# CAN.net
KiCad netlist of a schematic drawn in Altium Designer
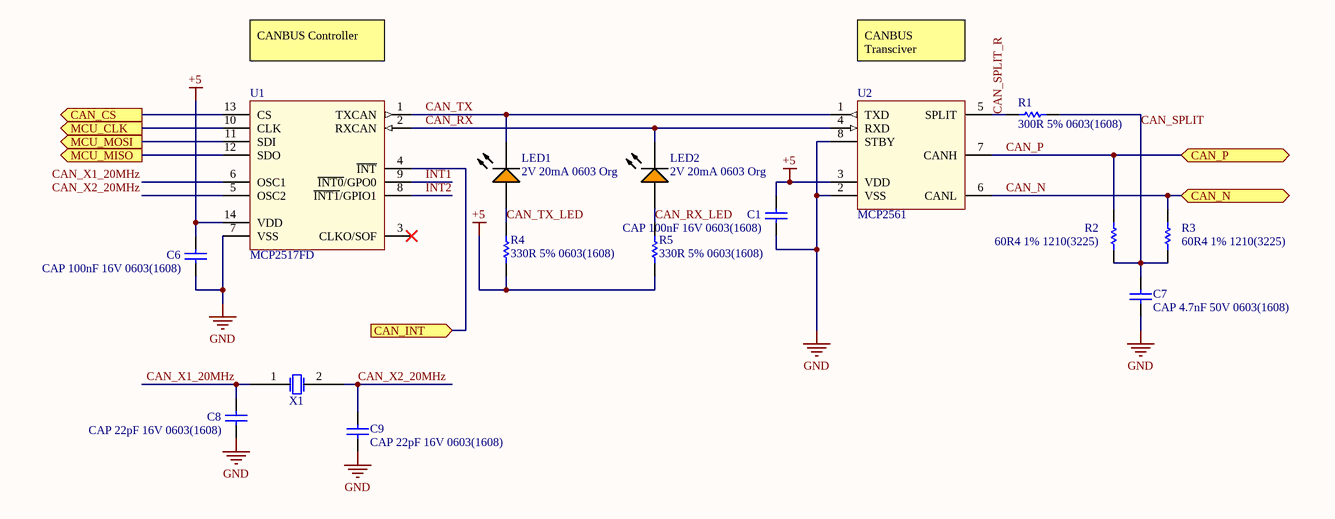
[diagram p0: CAN.SchDoc]

(export (version "E")
  (design (tool "Eeschema 10.0.6"))
  (components
    (comp (ref "C1")
      (value "CAP 100nF 16V 0603(1608)")
      (footprint "CAPC0603(1608)100_N")
      (description "CAP 100nF 16V ±10% 0603 (1608 Metric) Thickness 1mm SMD")
      (fields (field (name "TOLERANCE") "Â±10%"))
      (libsource (lib "Altium Content Vault") (part "CAP"))
    )
    (comp (ref "C6")
      (value "CAP 100nF 16V 0603(1608)")
      (footprint "CAPC0603(1608)100_N")
      (description "CAP 100nF 16V ±10% 0603 (1608 Metric) Thickness 1mm SMD")
      (fields (field (name "TOLERANCE") "Â±10%"))
      (libsource (lib "Altium Content Vault") (part "CAP"))
    )
    (comp (ref "C7")
      (value "CAP 4.7nF 50V 0603(1608)")
      (footprint "CAPC0603(1608)100_M")
      (description "CAP 4.7nF 50V ±5% 0603 (1608 Metric) Thickness 1mm SMD")
      (fields (field (name "TOLERANCE") "Â±5%"))
      (libsource (lib "Altium Content Vault") (part "CAP"))
    )
    (comp (ref "C8")
      (value "CAP 22pF 16V 0603(1608)")
      (footprint "CAPC0603(1608)100_N")
      (description "CAP 22pF 16V ±5% 0603 (1608 Metric) Thickness 1mm SMD")
      (fields (field (name "TOLERANCE") "Â±5%"))
      (libsource (lib "Altium Content Vault") (part "CAP"))
    )
    (comp (ref "C9")
      (value "CAP 22pF 16V 0603(1608)")
      (footprint "CAPC0603(1608)100_N")
      (description "CAP 22pF 16V ±5% 0603 (1608 Metric) Thickness 1mm SMD")
      (fields (field (name "TOLERANCE") "Â±5%"))
      (libsource (lib "Altium Content Vault") (part "CAP"))
    )
    (comp (ref "LED1")
      (value "2V 20mA 0603 Org")
      (footprint "KING-LED0603-25-ORANGE_V")
      (description "LED, SMT, 0603(1608), 0.25mm Tthickness, Super Bright Orange")
      (fields (field (name "PARTNUMBER") "APG1608SEKC/T"))
      (libsource (lib "Altium Content Vault") (part "KING-LED_ORANGE_A1K2-2"))
    )
    (comp (ref "LED2")
      (value "2V 20mA 0603 Org")
      (footprint "KING-LED0603-25-ORANGE_V")
      (description "LED, SMT, 0603(1608), 0.25mm Tthickness, Super Bright Orange")
      (fields (field (name "PARTNUMBER") "APG1608SEKC/T"))
      (libsource (lib "Altium Content Vault") (part "KING-LED_ORANGE_A1K2-2"))
    )
    (comp (ref "R1")
      (value "300R 5% 0603(1608)")
      (footprint "RESC0603(1608)_N")
      (description "300R 0.1W 5% 0603 (1608 Metric)  SMD")
      (fields (field (name "TOLERANCE") "5 %") (field (name "POWER") "0.1 W"))
      (libsource (lib "Altium Content Vault") (part "RES"))
    )
    (comp (ref "R2")
      (value "60R4 1% 1210(3225)")
      (footprint "RESC1210(3225)_L")
      (description "60R4 0.5W 1% 1210 (3225 Metric)  SMD")
      (fields (field (name "TOLERANCE") "1 %") (field (name "POWER") "0.5 W"))
      (libsource (lib "Altium Content Vault") (part "RES"))
    )
    (comp (ref "R3")
      (value "60R4 1% 1210(3225)")
      (footprint "RESC1210(3225)_L")
      (description "60R4 0.5W 1% 1210 (3225 Metric)  SMD")
      (fields (field (name "TOLERANCE") "1 %") (field (name "POWER") "0.5 W"))
      (libsource (lib "Altium Content Vault") (part "RES"))
    )
    (comp (ref "R4")
      (value "330R 5% 0603(1608)")
      (footprint "RESC0603(1608)_L")
      (description "330R 0.1W 5% 0603 (1608 Metric)  SMD")
      (fields (field (name "TOLERANCE") "5 %") (field (name "POWER") "0.1 W"))
      (libsource (lib "Altium Content Vault") (part "RES"))
    )
    (comp (ref "R5")
      (value "330R 5% 0603(1608)")
      (footprint "RESC0603(1608)_L")
      (description "330R 0.1W 5% 0603 (1608 Metric)  SMD")
      (fields (field (name "TOLERANCE") "5 %") (field (name "POWER") "0.1 W"))
      (libsource (lib "Altium Content Vault") (part "RES"))
    )
    (comp (ref "U1")
      (value "MCP2517FD")
      (footprint "MCP2517FD SOIC")
      (libsource (lib "QUTMS_CANLibrary") (part "MCP2517FD"))
    )
    (comp (ref "U2")
      (value "MCP2561")
      (footprint "MCP2561 SOIC")
      (libsource (lib "QUTMS_CANLibrary") (part "MCP2561"))
    )
    (comp (ref "X1")
      (value "Crystal 20MHz")
      (footprint "Crystal 20MHz")
      (libsource (lib "QUTMS_CrystalLibrary") (part "Crystal 20MHz"))
    )
  )
  (nets
    (net (code "1") (name "+5") (class "Default")
      (node (ref "C1") (pin "2") (pinfunction "2_2") (pintype "passive"))
      (node (ref "C6") (pin "2") (pinfunction "2_2") (pintype "passive"))
      (node (ref "R4") (pin "2") (pinfunction "2_2") (pintype "passive"))
      (node (ref "R5") (pin "2") (pinfunction "2_2") (pintype "passive"))
      (node (ref "U1") (pin "14") (pinfunction "VDD_14") (pintype "passive"))
      (node (ref "U2") (pin "3") (pinfunction "VDD_3") (pintype "passive"))
    )
    (net (code "2") (name "/CAN_CS") (class "Default")
      (node (ref "U1") (pin "13") (pinfunction "CS_13") (pintype "passive"))
    )
    (net (code "3") (name "/CAN_INT") (class "Default")
      (node (ref "U1") (pin "4") (pinfunction "~{INT}_4") (pintype "passive"))
    )
    (net (code "4") (name "/CAN_N") (class "Default")
      (node (ref "R3") (pin "2") (pinfunction "2_2") (pintype "passive"))
      (node (ref "U2") (pin "6") (pinfunction "CANL_6") (pintype "passive"))
    )
    (net (code "5") (name "/CAN_P") (class "Default")
      (node (ref "R2") (pin "2") (pinfunction "2_2") (pintype "passive"))
      (node (ref "U2") (pin "7") (pinfunction "CANH_7") (pintype "passive"))
    )
    (net (code "6") (name "/CAN_RX") (class "Default")
      (node (ref "LED2") (pin "2") (pinfunction "K_2") (pintype "passive"))
      (node (ref "U1") (pin "2") (pinfunction "RXCAN_2") (pintype "input"))
      (node (ref "U2") (pin "4") (pinfunction "RXD_4") (pintype "input"))
    )
    (net (code "7") (name "/CAN_RX_LED") (class "Default")
      (node (ref "LED2") (pin "1") (pinfunction "A_1") (pintype "passive"))
      (node (ref "R5") (pin "1") (pinfunction "1_1") (pintype "passive"))
    )
    (net (code "8") (name "/CAN_SPLIT") (class "Default")
      (node (ref "C7") (pin "2") (pinfunction "2_2") (pintype "passive"))
      (node (ref "R1") (pin "2") (pinfunction "2_2") (pintype "passive"))
      (node (ref "R2") (pin "1") (pinfunction "1_1") (pintype "passive"))
      (node (ref "R3") (pin "1") (pinfunction "1_1") (pintype "passive"))
    )
    (net (code "9") (name "/CAN_SPLIT_R") (class "Default")
      (node (ref "R1") (pin "1") (pinfunction "1_1") (pintype "passive"))
      (node (ref "U2") (pin "5") (pinfunction "SPLIT_5") (pintype "passive"))
    )
    (net (code "10") (name "/CAN_TX") (class "Default")
      (node (ref "LED1") (pin "2") (pinfunction "K_2") (pintype "passive"))
      (node (ref "U1") (pin "1") (pinfunction "TXCAN_1") (pintype "output"))
      (node (ref "U2") (pin "1") (pinfunction "TXD_1") (pintype "output"))
    )
    (net (code "11") (name "/CAN_TX_LED") (class "Default")
      (node (ref "LED1") (pin "1") (pinfunction "A_1") (pintype "passive"))
      (node (ref "R4") (pin "1") (pinfunction "1_1") (pintype "passive"))
    )
    (net (code "12") (name "/CAN_X1_20MHz") (class "Default")
      (node (ref "C8") (pin "2") (pinfunction "2_2") (pintype "passive"))
      (node (ref "U1") (pin "6") (pinfunction "OSC1_6") (pintype "passive"))
      (node (ref "X1") (pin "1") (pintype "passive"))
    )
    (net (code "13") (name "/CAN_X2_20MHz") (class "Default")
      (node (ref "C9") (pin "1") (pinfunction "1_1") (pintype "passive"))
      (node (ref "U1") (pin "5") (pinfunction "OSC2_5") (pintype "passive"))
      (node (ref "X1") (pin "2") (pintype "passive"))
    )
    (net (code "14") (name "/INT1") (class "Default")
      (node (ref "U1") (pin "9") (pinfunction "~{INT0}/GPO0_9") (pintype "passive"))
    )
    (net (code "15") (name "/INT2") (class "Default")
      (node (ref "U1") (pin "8") (pinfunction "~{INT1}/GPIO1_8") (pintype "passive"))
    )
    (net (code "16") (name "/MCU_CLK") (class "Default")
      (node (ref "U1") (pin "10") (pinfunction "CLK_10") (pintype "passive"))
    )
    (net (code "17") (name "/MCU_MISO") (class "Default")
      (node (ref "U1") (pin "12") (pinfunction "SDO_12") (pintype "passive"))
    )
    (net (code "18") (name "/MCU_MOSI") (class "Default")
      (node (ref "U1") (pin "11") (pinfunction "SDI_11") (pintype "passive"))
    )
    (net (code "19") (name "GND") (class "Default")
      (node (ref "C1") (pin "1") (pinfunction "1_1") (pintype "passive"))
      (node (ref "C6") (pin "1") (pinfunction "1_1") (pintype "passive"))
      (node (ref "C7") (pin "1") (pinfunction "1_1") (pintype "passive"))
      (node (ref "C8") (pin "1") (pinfunction "1_1") (pintype "passive"))
      (node (ref "C9") (pin "2") (pinfunction "2_2") (pintype "passive"))
      (node (ref "U1") (pin "7") (pinfunction "VSS_7") (pintype "passive"))
      (node (ref "U2") (pin "2") (pinfunction "VSS_2") (pintype "passive"))
      (node (ref "U2") (pin "8") (pinfunction "STBY_8") (pintype "passive"))
    )
    (net (code "20") (name "unconnected-(U1-CLKO{slash}SOF-Pad3)") (class "Default")
      (node (ref "U1") (pin "3") (pinfunction "CLKO/SOF_3") (pintype "passive+no_connect"))
    )
  )
)
